# mb.net
KiCad netlist of a schematic drawn in EAGLE
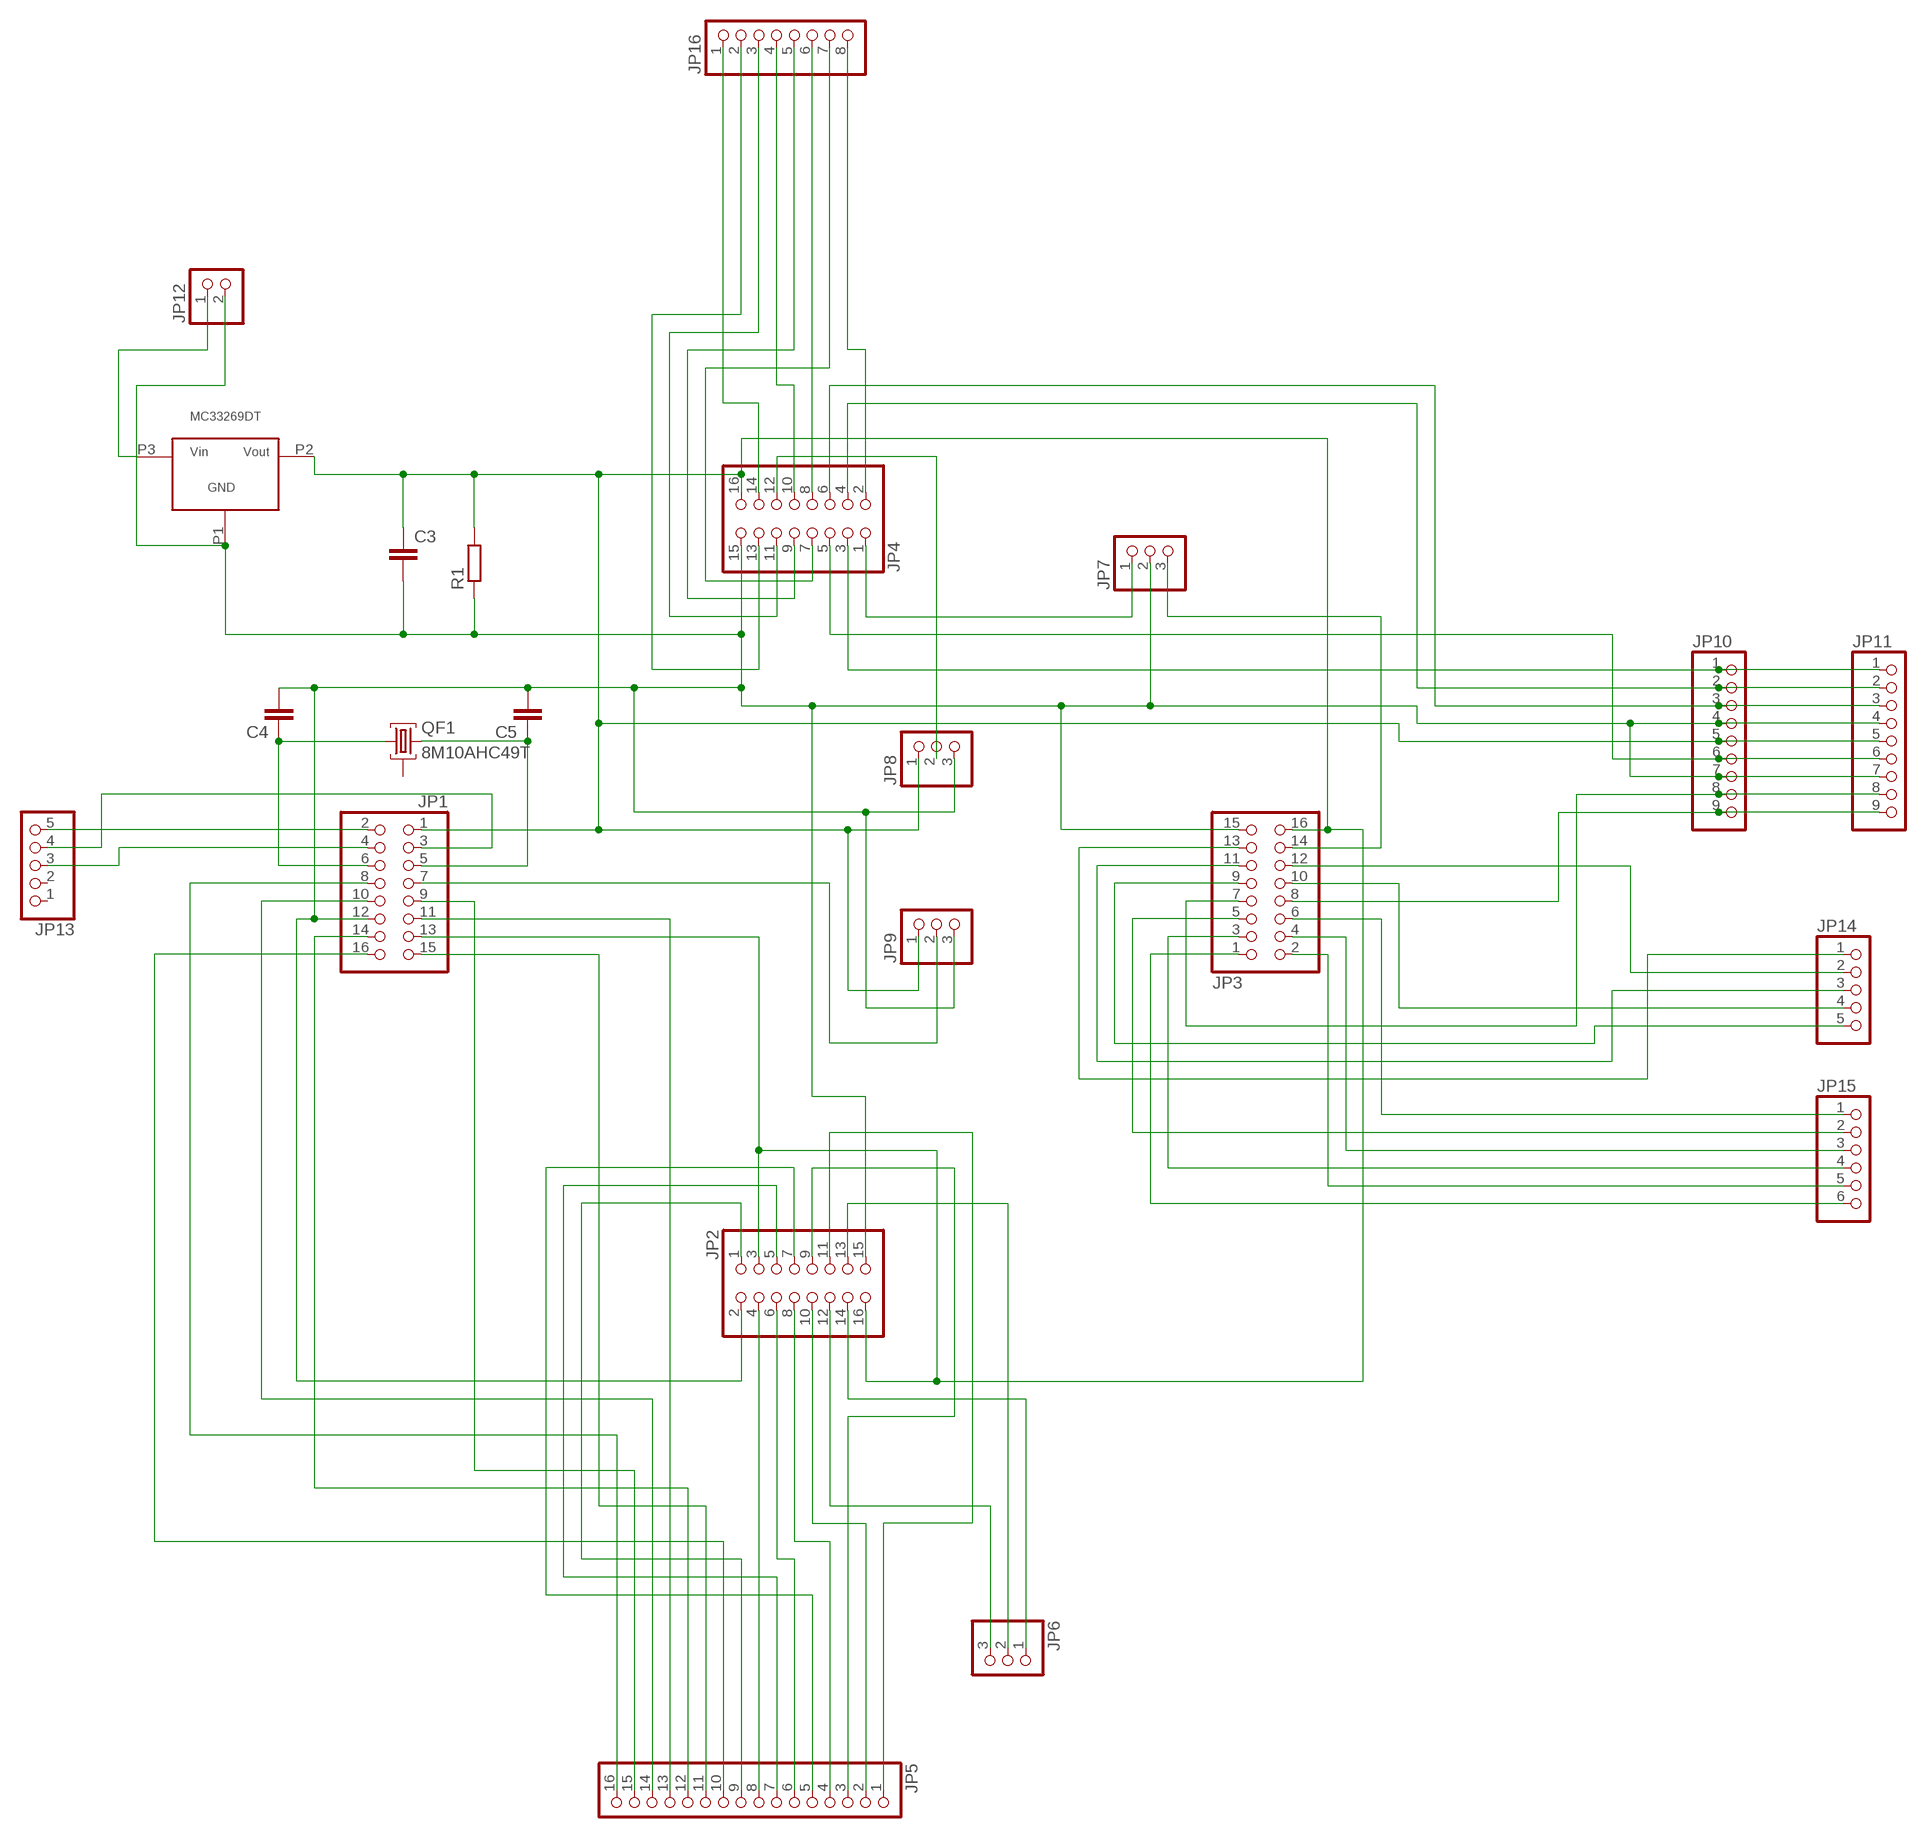
[diagram p0: schematic, sheet 1]

(export (version "E")
  (design (tool "Eeschema 10.0.6"))
  (components
    (comp (ref "C3")
      (value "C5/2.5")
      (footprint "eagle-import:C5B2.5")
      (libsource (lib "eagle-import") (part "C5/2.5"))
    )
    (comp (ref "C4")
      (value "C-EUC1206")
      (footprint "eagle-import:C1206")
      (libsource (lib "eagle-import") (part "C-EUC1206"))
    )
    (comp (ref "C5")
      (value "C-EUC1206")
      (footprint "eagle-import:C1206")
      (libsource (lib "eagle-import") (part "C-EUC1206"))
    )
    (comp (ref "JP1")
      (value "PINHD-2X8")
      (footprint "eagle-import:2X08")
      (libsource (lib "eagle-import") (part "PINHD-2X8"))
    )
    (comp (ref "JP2")
      (value "PINHD-2X8")
      (footprint "eagle-import:2X08")
      (libsource (lib "eagle-import") (part "PINHD-2X8"))
    )
    (comp (ref "JP3")
      (value "PINHD-2X8")
      (footprint "eagle-import:2X08")
      (libsource (lib "eagle-import") (part "PINHD-2X8"))
    )
    (comp (ref "JP4")
      (value "PINHD-2X8")
      (footprint "eagle-import:2X08")
      (libsource (lib "eagle-import") (part "PINHD-2X8"))
    )
    (comp (ref "JP5")
      (value "PINHD-1X16")
      (footprint "eagle-import:1X16")
      (libsource (lib "eagle-import") (part "PINHD-1X16"))
    )
    (comp (ref "JP6")
      (value "PINHD-1X3")
      (footprint "eagle-import:1X03")
      (libsource (lib "eagle-import") (part "PINHD-1X3"))
    )
    (comp (ref "JP7")
      (value "PINHD-1X3")
      (footprint "eagle-import:1X03")
      (libsource (lib "eagle-import") (part "PINHD-1X3"))
    )
    (comp (ref "JP8")
      (value "PINHD-1X3")
      (footprint "eagle-import:1X03")
      (libsource (lib "eagle-import") (part "PINHD-1X3"))
    )
    (comp (ref "JP9")
      (value "PINHD-1X3")
      (footprint "eagle-import:1X03")
      (libsource (lib "eagle-import") (part "PINHD-1X3"))
    )
    (comp (ref "JP10")
      (value "PINHD-1X9")
      (footprint "eagle-import:1X09")
      (libsource (lib "eagle-import") (part "PINHD-1X9"))
    )
    (comp (ref "JP11")
      (value "PINHD-1X9")
      (footprint "eagle-import:1X09")
      (libsource (lib "eagle-import") (part "PINHD-1X9"))
    )
    (comp (ref "JP12")
      (value "PINHD-1X2")
      (footprint "eagle-import:1X02")
      (libsource (lib "eagle-import") (part "PINHD-1X2"))
    )
    (comp (ref "JP13")
      (value "PINHD-1X5")
      (footprint "eagle-import:1X05")
      (libsource (lib "eagle-import") (part "PINHD-1X5"))
    )
    (comp (ref "JP14")
      (value "PINHD-1X5")
      (footprint "eagle-import:1X05")
      (libsource (lib "eagle-import") (part "PINHD-1X5"))
    )
    (comp (ref "JP15")
      (value "PINHD-1X6")
      (footprint "eagle-import:1X06")
      (libsource (lib "eagle-import") (part "PINHD-1X6"))
    )
    (comp (ref "JP16")
      (value "PINHD-1X8")
      (footprint "eagle-import:1X08")
      (libsource (lib "eagle-import") (part "PINHD-1X8"))
    )
    (comp (ref "QF1")
      (value "8M10AHC49T")
      (footprint "eagle-import:HC49U")
      (libsource (lib "eagle-import") (part "8M10AHC49T"))
    )
    (comp (ref "R1")
      (value "R-EU_M1206")
      (footprint "eagle-import:M1206")
      (libsource (lib "eagle-import") (part "R-EU_M1206"))
    )
    (comp (ref "U$1")
      (value "MC33269DT")
      (footprint "eagle-import:MC33269DT")
      (libsource (lib "eagle-import") (part "MC33269DT"))
    )
  )
  (nets
    (net (code "1") (name "Net-(C4-Pad1)") (class "Default")
      (node (ref "C4") (pin "1") (pinfunction "1_1") (pintype "passive"))
      (node (ref "JP1") (pin "6") (pinfunction "6_6") (pintype "passive"))
      (node (ref "QF1") (pin "1") (pinfunction "1_1") (pintype "passive"))
    )
    (net (code "2") (name "Net-(C5-Pad1)") (class "Default")
      (node (ref "C5") (pin "1") (pinfunction "1_1") (pintype "passive"))
      (node (ref "JP1") (pin "5") (pinfunction "5_5") (pintype "passive"))
      (node (ref "QF1") (pin "3") (pinfunction "3_3") (pintype "passive"))
    )
    (net (code "3") (name "Net-(JP1-Pad2)") (class "Default")
      (node (ref "JP1") (pin "2") (pinfunction "2_2") (pintype "passive"))
      (node (ref "JP13") (pin "5") (pinfunction "5_5") (pintype "passive"))
    )
    (net (code "4") (name "Net-(JP1-Pad3)") (class "Default")
      (node (ref "JP1") (pin "3") (pinfunction "3_3") (pintype "passive"))
      (node (ref "JP13") (pin "4") (pinfunction "4_4") (pintype "passive"))
    )
    (net (code "5") (name "Net-(JP1-Pad4)") (class "Default")
      (node (ref "JP1") (pin "4") (pinfunction "4_4") (pintype "passive"))
      (node (ref "JP13") (pin "3") (pinfunction "3_3") (pintype "passive"))
    )
    (net (code "6") (name "Net-(JP1-Pad7)") (class "Default")
      (node (ref "JP1") (pin "7") (pinfunction "7_7") (pintype "passive"))
      (node (ref "JP9") (pin "2") (pinfunction "2_2") (pintype "passive"))
    )
    (net (code "7") (name "Net-(JP1-Pad8)") (class "Default")
      (node (ref "JP1") (pin "8") (pinfunction "8_8") (pintype "passive"))
      (node (ref "JP5") (pin "16") (pinfunction "16_16") (pintype "passive"))
    )
    (net (code "8") (name "Net-(JP1-Pad9)") (class "Default")
      (node (ref "JP1") (pin "9") (pinfunction "9_9") (pintype "passive"))
      (node (ref "JP5") (pin "15") (pinfunction "15_15") (pintype "passive"))
    )
    (net (code "9") (name "Net-(JP1-Pad10)") (class "Default")
      (node (ref "JP1") (pin "10") (pinfunction "10_10") (pintype "passive"))
      (node (ref "JP5") (pin "14") (pinfunction "14_14") (pintype "passive"))
    )
    (net (code "10") (name "Net-(JP1-Pad11)") (class "Default")
      (node (ref "JP1") (pin "11") (pinfunction "11_11") (pintype "passive"))
      (node (ref "JP5") (pin "13") (pinfunction "13_13") (pintype "passive"))
    )
    (net (code "11") (name "Net-(JP1-Pad14)") (class "Default")
      (node (ref "JP1") (pin "14") (pinfunction "14_14") (pintype "passive"))
      (node (ref "JP5") (pin "12") (pinfunction "12_12") (pintype "passive"))
    )
    (net (code "12") (name "Net-(JP1-Pad15)") (class "Default")
      (node (ref "JP1") (pin "15") (pinfunction "15_15") (pintype "passive"))
      (node (ref "JP5") (pin "11") (pinfunction "11_11") (pintype "passive"))
    )
    (net (code "13") (name "Net-(JP1-Pad16)") (class "Default")
      (node (ref "JP1") (pin "16") (pinfunction "16_16") (pintype "passive"))
      (node (ref "JP5") (pin "10") (pinfunction "10_10") (pintype "passive"))
    )
    (net (code "14") (name "Net-(JP2-Pad1)") (class "Default")
      (node (ref "JP2") (pin "1") (pinfunction "1_1") (pintype "passive"))
      (node (ref "JP5") (pin "9") (pinfunction "9_9") (pintype "passive"))
    )
    (net (code "15") (name "Net-(JP2-Pad4)") (class "Default")
      (node (ref "JP2") (pin "4") (pinfunction "4_4") (pintype "passive"))
      (node (ref "JP5") (pin "8") (pinfunction "8_8") (pintype "passive"))
    )
    (net (code "16") (name "Net-(JP2-Pad5)") (class "Default")
      (node (ref "JP2") (pin "5") (pinfunction "5_5") (pintype "passive"))
      (node (ref "JP5") (pin "7") (pinfunction "7_7") (pintype "passive"))
    )
    (net (code "17") (name "Net-(JP2-Pad6)") (class "Default")
      (node (ref "JP2") (pin "6") (pinfunction "6_6") (pintype "passive"))
      (node (ref "JP5") (pin "6") (pinfunction "6_6") (pintype "passive"))
    )
    (net (code "18") (name "Net-(JP2-Pad7)") (class "Default")
      (node (ref "JP2") (pin "7") (pinfunction "7_7") (pintype "passive"))
      (node (ref "JP5") (pin "5") (pinfunction "5_5") (pintype "passive"))
    )
    (net (code "19") (name "Net-(JP2-Pad8)") (class "Default")
      (node (ref "JP2") (pin "8") (pinfunction "8_8") (pintype "passive"))
      (node (ref "JP5") (pin "4") (pinfunction "4_4") (pintype "passive"))
    )
    (net (code "20") (name "Net-(JP2-Pad9)") (class "Default")
      (node (ref "JP2") (pin "9") (pinfunction "9_9") (pintype "passive"))
      (node (ref "JP5") (pin "3") (pinfunction "3_3") (pintype "passive"))
    )
    (net (code "21") (name "Net-(JP2-Pad10)") (class "Default")
      (node (ref "JP2") (pin "10") (pinfunction "10_10") (pintype "passive"))
      (node (ref "JP5") (pin "2") (pinfunction "2_2") (pintype "passive"))
    )
    (net (code "22") (name "Net-(JP2-Pad11)") (class "Default")
      (node (ref "JP2") (pin "11") (pinfunction "11_11") (pintype "passive"))
      (node (ref "JP5") (pin "1") (pinfunction "1_1") (pintype "passive"))
    )
    (net (code "23") (name "Net-(JP2-Pad12)") (class "Default")
      (node (ref "JP2") (pin "12") (pinfunction "12_12") (pintype "passive"))
      (node (ref "JP6") (pin "3") (pinfunction "3_3") (pintype "passive"))
    )
    (net (code "24") (name "Net-(JP2-Pad13)") (class "Default")
      (node (ref "JP2") (pin "13") (pinfunction "13_13") (pintype "passive"))
      (node (ref "JP6") (pin "2") (pinfunction "2_2") (pintype "passive"))
    )
    (net (code "25") (name "Net-(JP2-Pad14)") (class "Default")
      (node (ref "JP2") (pin "14") (pinfunction "14_14") (pintype "passive"))
      (node (ref "JP6") (pin "1") (pinfunction "1_1") (pintype "passive"))
    )
    (net (code "26") (name "Net-(JP3-Pad14)") (class "Default")
      (node (ref "JP3") (pin "14") (pinfunction "14_14") (pintype "passive"))
      (node (ref "JP7") (pin "3") (pinfunction "3_3") (pintype "passive"))
    )
    (net (code "27") (name "Net-(JP4-Pad1)") (class "Default")
      (node (ref "JP4") (pin "1") (pinfunction "1_1") (pintype "passive"))
      (node (ref "JP7") (pin "1") (pinfunction "1_1") (pintype "passive"))
    )
    (net (code "28") (name "Net-(JP4-Pad12)") (class "Default")
      (node (ref "JP4") (pin "12") (pinfunction "12_12") (pintype "passive"))
      (node (ref "JP8") (pin "2") (pinfunction "2_2") (pintype "passive"))
    )
    (net (code "29") (name "Net-(JP10-Pad1)") (class "Default")
      (node (ref "JP10") (pin "1") (pinfunction "1_1") (pintype "passive"))
      (node (ref "JP11") (pin "1") (pinfunction "1_1") (pintype "passive"))
      (node (ref "JP4") (pin "3") (pinfunction "3_3") (pintype "passive"))
    )
    (net (code "30") (name "Net-(JP10-Pad2)") (class "Default")
      (node (ref "JP10") (pin "2") (pinfunction "2_2") (pintype "passive"))
      (node (ref "JP11") (pin "2") (pinfunction "2_2") (pintype "passive"))
      (node (ref "JP4") (pin "4") (pinfunction "4_4") (pintype "passive"))
    )
    (net (code "31") (name "Net-(JP10-Pad3)") (class "Default")
      (node (ref "JP10") (pin "3") (pinfunction "3_3") (pintype "passive"))
      (node (ref "JP11") (pin "3") (pinfunction "3_3") (pintype "passive"))
      (node (ref "JP4") (pin "6") (pinfunction "6_6") (pintype "passive"))
    )
    (net (code "32") (name "Net-(JP10-Pad6)") (class "Default")
      (node (ref "JP10") (pin "6") (pinfunction "6_6") (pintype "passive"))
      (node (ref "JP11") (pin "6") (pinfunction "6_6") (pintype "passive"))
      (node (ref "JP4") (pin "5") (pinfunction "5_5") (pintype "passive"))
    )
    (net (code "33") (name "Net-(JP10-Pad8)") (class "Default")
      (node (ref "JP10") (pin "8") (pinfunction "8_8") (pintype "passive"))
      (node (ref "JP11") (pin "8") (pinfunction "8_8") (pintype "passive"))
      (node (ref "JP3") (pin "7") (pinfunction "7_7") (pintype "passive"))
    )
    (net (code "34") (name "Net-(JP10-Pad9)") (class "Default")
      (node (ref "JP10") (pin "9") (pinfunction "9_9") (pintype "passive"))
      (node (ref "JP11") (pin "9") (pinfunction "9_9") (pintype "passive"))
      (node (ref "JP3") (pin "8") (pinfunction "8_8") (pintype "passive"))
    )
    (net (code "35") (name "Net-(JP14-Pad1)") (class "Default")
      (node (ref "JP14") (pin "1") (pinfunction "1_1") (pintype "passive"))
      (node (ref "JP3") (pin "13") (pinfunction "13_13") (pintype "passive"))
    )
    (net (code "36") (name "Net-(JP14-Pad2)") (class "Default")
      (node (ref "JP14") (pin "2") (pinfunction "2_2") (pintype "passive"))
      (node (ref "JP3") (pin "12") (pinfunction "12_12") (pintype "passive"))
    )
    (net (code "37") (name "Net-(JP14-Pad3)") (class "Default")
      (node (ref "JP14") (pin "3") (pinfunction "3_3") (pintype "passive"))
      (node (ref "JP3") (pin "11") (pinfunction "11_11") (pintype "passive"))
    )
    (net (code "38") (name "Net-(JP14-Pad4)") (class "Default")
      (node (ref "JP14") (pin "4") (pinfunction "4_4") (pintype "passive"))
      (node (ref "JP3") (pin "10") (pinfunction "10_10") (pintype "passive"))
    )
    (net (code "39") (name "Net-(JP14-Pad5)") (class "Default")
      (node (ref "JP14") (pin "5") (pinfunction "5_5") (pintype "passive"))
      (node (ref "JP3") (pin "9") (pinfunction "9_9") (pintype "passive"))
    )
    (net (code "40") (name "Net-(JP15-Pad1)") (class "Default")
      (node (ref "JP15") (pin "1") (pinfunction "1_1") (pintype "passive"))
      (node (ref "JP3") (pin "6") (pinfunction "6_6") (pintype "passive"))
    )
    (net (code "41") (name "Net-(JP15-Pad2)") (class "Default")
      (node (ref "JP15") (pin "2") (pinfunction "2_2") (pintype "passive"))
      (node (ref "JP3") (pin "5") (pinfunction "5_5") (pintype "passive"))
    )
    (net (code "42") (name "Net-(JP15-Pad3)") (class "Default")
      (node (ref "JP15") (pin "3") (pinfunction "3_3") (pintype "passive"))
      (node (ref "JP3") (pin "4") (pinfunction "4_4") (pintype "passive"))
    )
    (net (code "43") (name "Net-(JP15-Pad4)") (class "Default")
      (node (ref "JP15") (pin "4") (pinfunction "4_4") (pintype "passive"))
      (node (ref "JP3") (pin "3") (pinfunction "3_3") (pintype "passive"))
    )
    (net (code "44") (name "Net-(JP15-Pad5)") (class "Default")
      (node (ref "JP15") (pin "5") (pinfunction "5_5") (pintype "passive"))
      (node (ref "JP3") (pin "2") (pinfunction "2_2") (pintype "passive"))
    )
    (net (code "45") (name "Net-(JP15-Pad6)") (class "Default")
      (node (ref "JP15") (pin "6") (pinfunction "6_6") (pintype "passive"))
      (node (ref "JP3") (pin "1") (pinfunction "1_1") (pintype "passive"))
    )
    (net (code "46") (name "Net-(JP16-Pad1)") (class "Default")
      (node (ref "JP16") (pin "1") (pinfunction "1_1") (pintype "passive"))
      (node (ref "JP4") (pin "14") (pinfunction "14_14") (pintype "passive"))
    )
    (net (code "47") (name "Net-(JP16-Pad2)") (class "Default")
      (node (ref "JP16") (pin "2") (pinfunction "2_2") (pintype "passive"))
      (node (ref "JP4") (pin "13") (pinfunction "13_13") (pintype "passive"))
    )
    (net (code "48") (name "Net-(JP16-Pad3)") (class "Default")
      (node (ref "JP16") (pin "3") (pinfunction "3_3") (pintype "passive"))
      (node (ref "JP4") (pin "11") (pinfunction "11_11") (pintype "passive"))
    )
    (net (code "49") (name "Net-(JP16-Pad4)") (class "Default")
      (node (ref "JP16") (pin "4") (pinfunction "4_4") (pintype "passive"))
      (node (ref "JP4") (pin "10") (pinfunction "10_10") (pintype "passive"))
    )
    (net (code "50") (name "Net-(JP16-Pad5)") (class "Default")
      (node (ref "JP16") (pin "5") (pinfunction "5_5") (pintype "passive"))
      (node (ref "JP4") (pin "9") (pinfunction "9_9") (pintype "passive"))
    )
    (net (code "51") (name "Net-(JP16-Pad6)") (class "Default")
      (node (ref "JP16") (pin "6") (pinfunction "6_6") (pintype "passive"))
      (node (ref "JP4") (pin "8") (pinfunction "8_8") (pintype "passive"))
    )
    (net (code "52") (name "Net-(JP16-Pad7)") (class "Default")
      (node (ref "JP16") (pin "7") (pinfunction "7_7") (pintype "passive"))
      (node (ref "JP4") (pin "7") (pinfunction "7_7") (pintype "passive"))
    )
    (net (code "53") (name "Net-(JP16-Pad8)") (class "Default")
      (node (ref "JP16") (pin "8") (pinfunction "8_8") (pintype "passive"))
      (node (ref "JP4") (pin "2") (pinfunction "2_2") (pintype "passive"))
    )
    (net (code "54") (name "Net-(U$1-GND)") (class "Default")
      (node (ref "C3") (pin "2") (pinfunction "2_2") (pintype "passive"))
      (node (ref "C4") (pin "2") (pinfunction "2_2") (pintype "passive"))
      (node (ref "C5") (pin "2") (pinfunction "2_2") (pintype "passive"))
      (node (ref "JP1") (pin "12") (pinfunction "12_12") (pintype "passive"))
      (node (ref "JP10") (pin "4") (pinfunction "4_4") (pintype "passive"))
      (node (ref "JP10") (pin "7") (pinfunction "7_7") (pintype "passive"))
      (node (ref "JP11") (pin "4") (pinfunction "4_4") (pintype "passive"))
      (node (ref "JP11") (pin "7") (pinfunction "7_7") (pintype "passive"))
      (node (ref "JP12") (pin "2") (pinfunction "2_2") (pintype "passive"))
      (node (ref "JP2") (pin "15") (pinfunction "15_15") (pintype "passive"))
      (node (ref "JP2") (pin "2") (pinfunction "2_2") (pintype "passive"))
      (node (ref "JP3") (pin "15") (pinfunction "15_15") (pintype "passive"))
      (node (ref "JP4") (pin "15") (pinfunction "15_15") (pintype "passive"))
      (node (ref "JP7") (pin "2") (pinfunction "2_2") (pintype "passive"))
      (node (ref "JP8") (pin "3") (pinfunction "3_3") (pintype "passive"))
      (node (ref "JP9") (pin "3") (pinfunction "3_3") (pintype "passive"))
      (node (ref "R1") (pin "1") (pinfunction "1_1") (pintype "passive"))
      (node (ref "U$1") (pin "P1") (pinfunction "GND_P1") (pintype "power_in"))
    )
    (net (code "55") (name "Net-(U$1-VIN)") (class "Default")
      (node (ref "JP12") (pin "1") (pinfunction "1_1") (pintype "passive"))
      (node (ref "U$1") (pin "P3") (pinfunction "VIN_P3") (pintype "input"))
    )
    (net (code "56") (name "Net-(U$1-VOUT)") (class "Default")
      (node (ref "C3") (pin "1") (pinfunction "1_1") (pintype "passive"))
      (node (ref "JP1") (pin "1") (pinfunction "1_1") (pintype "passive"))
      (node (ref "JP1") (pin "13") (pinfunction "13_13") (pintype "passive"))
      (node (ref "JP10") (pin "5") (pinfunction "5_5") (pintype "passive"))
      (node (ref "JP11") (pin "5") (pinfunction "5_5") (pintype "passive"))
      (node (ref "JP2") (pin "16") (pinfunction "16_16") (pintype "passive"))
      (node (ref "JP2") (pin "3") (pinfunction "3_3") (pintype "passive"))
      (node (ref "JP3") (pin "16") (pinfunction "16_16") (pintype "passive"))
      (node (ref "JP4") (pin "16") (pinfunction "16_16") (pintype "passive"))
      (node (ref "JP8") (pin "1") (pinfunction "1_1") (pintype "passive"))
      (node (ref "JP9") (pin "1") (pinfunction "1_1") (pintype "passive"))
      (node (ref "R1") (pin "2") (pinfunction "2_2") (pintype "passive"))
      (node (ref "U$1") (pin "P2") (pinfunction "VOUT_P2") (pintype "output"))
    )
    (net (code "57") (name "unconnected-(JP13-Pad1)") (class "Default")
      (node (ref "JP13") (pin "1") (pinfunction "1_1") (pintype "passive"))
    )
    (net (code "58") (name "unconnected-(JP13-Pad2)") (class "Default")
      (node (ref "JP13") (pin "2") (pinfunction "2_2") (pintype "passive"))
    )
    (net (code "59") (name "unconnected-(QF1-Pad2)") (class "Default")
      (node (ref "QF1") (pin "2") (pinfunction "2_2") (pintype "passive"))
    )
  )
)
